# Rajesh_Jasti_17978253_Lab_1.net
KiCad netlist of a schematic drawn in Altium Designer
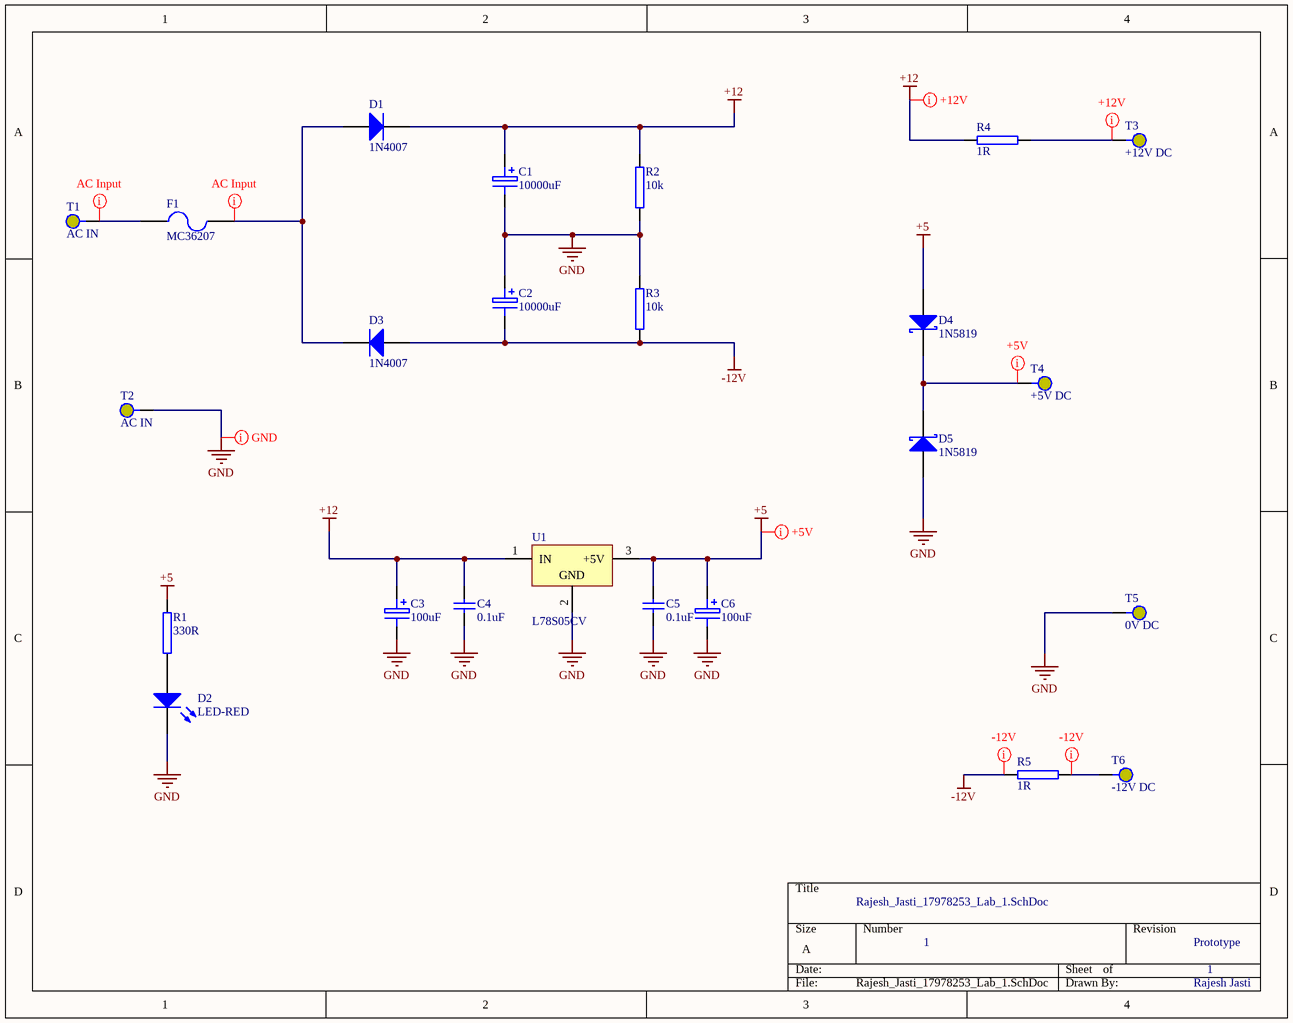
[diagram p0: Rajesh_Jasti_17978253_Lab_1.SchDoc]

(export (version "E")
  (design (tool "Eeschema 10.0.6"))
  (components
    (comp (ref "C1")
      (value "10000uF")
      (footprint "CAPP18-7.5mm")
      (description "Polarized Aluminum Capacitor, Through Hole, Pitch 7.5mml, Body 18mm(Dia)")
      (libsource (lib "Resistors and Capacitors") (part "CAPACITOR 10000uF"))
    )
    (comp (ref "C2")
      (value "10000uF")
      (footprint "CAPP18-7.5mm")
      (description "Polarized Aluminum Capacitor, Through Hole, Pitch 7.5mml, Body 18mm(Dia)")
      (libsource (lib "Resistors and Capacitors") (part "CAPACITOR 10000uF"))
    )
    (comp (ref "C3")
      (value "100uF")
      (footprint "CAPP150-300_AUT")
      (description "Polarized Aluminum Capacitor, Through Hole, Pitch 150mil, Body 300mil (Dia)")
      (libsource (lib "Resistors and Capacitors") (part "CAPP150-300"))
    )
    (comp (ref "C4")
      (value "0.1uF")
      (footprint "RAD-0.1_AUT")
      (description "Non Polarized Capacitor, Multilayer Ceramic Dipped Radial, Pitch 100mil")
      (libsource (lib "Resistors and Capacitors") (part "CAPN RAD0.1"))
    )
    (comp (ref "C5")
      (value "0.1uF")
      (footprint "RAD-0.1_AUT")
      (description "Non Polarized Capacitor, Multilayer Ceramic Dipped Radial, Pitch 100mil")
      (libsource (lib "Resistors and Capacitors") (part "CAPN RAD0.1"))
    )
    (comp (ref "C6")
      (value "100uF")
      (footprint "CAPP150-300_AUT")
      (description "Polarized Aluminum Capacitor, Through Hole, Pitch 150mil, Body 300mil (Dia)")
      (libsource (lib "Resistors and Capacitors") (part "CAPP150-300"))
    )
    (comp (ref "D1")
      (value "1N4007")
      (footprint "DIODE0.4_AUT")
      (description "Diode, Standard, 1A, 1000v")
      (libsource (lib "Diodes") (part "1N4007"))
    )
    (comp (ref "D2")
      (value "LED-RED")
      (footprint "LED3MM_R_AUT")
      (description "3mm RED LED, Through Hole")
      (libsource (lib "LEDs") (part "3mm LED-RED"))
    )
    (comp (ref "D3")
      (value "1N4007")
      (footprint "DIODE0.4_AUT")
      (description "Diode, Standard, 1A, 1000v")
      (libsource (lib "Diodes") (part "1N4007"))
    )
    (comp (ref "D4")
      (value "1N5819")
      (footprint "DIODE0.4_AUT")
      (description "Schottky Diode, 1A,40v")
      (libsource (lib "Diodes") (part "1N5819"))
    )
    (comp (ref "D5")
      (value "1N5819")
      (footprint "DIODE0.4_AUT")
      (description "Schottky Diode, 1A,40v")
      (libsource (lib "Diodes") (part "1N5819"))
    )
    (comp (ref "F1")
      (value "MC36207")
      (footprint "MC36207")
      (description "Fuse, PTC Reset, 200mA Hold, 400mA Tripping, 30v")
      (libsource (lib "Fuses") (part "MC36207"))
    )
    (comp (ref "R1")
      (value "330R")
      (footprint "AXIAL-0.4AUT")
      (description "Resistor, Through Hole, Pitch 400mil")
      (libsource (lib "Resistors and Capacitors") (part "Resistor 1/4W"))
    )
    (comp (ref "R2")
      (value "10k")
      (footprint "AXIAL-0.4AUT")
      (description "Resistor, Through Hole, Pitch 400mil")
      (libsource (lib "Resistors and Capacitors") (part "Resistor 1/4W"))
    )
    (comp (ref "R3")
      (value "10k")
      (footprint "AXIAL-0.4AUT")
      (description "Resistor, Through Hole, Pitch 400mil")
      (libsource (lib "Resistors and Capacitors") (part "Resistor 1/4W"))
    )
    (comp (ref "R4")
      (value "1R")
      (footprint "AXIAL-0.5AUT")
      (description "Resistor, Through Hole, Pitch 500mil")
      (libsource (lib "Resistors and Capacitors") (part "Resistor 1/2W"))
    )
    (comp (ref "R5")
      (value "1R")
      (footprint "AXIAL-0.5AUT")
      (description "Resistor, Through Hole, Pitch 500mil")
      (libsource (lib "Resistors and Capacitors") (part "Resistor 1/2W"))
    )
    (comp (ref "T1")
      (value "AC IN")
      (footprint "PAD3_AUT")
      (description "Terminal, Pad 200x250mil, Hole 62mil")
      (libsource (lib "Connectors") (part "Terminal3"))
    )
    (comp (ref "T2")
      (value "AC IN")
      (footprint "PAD3_AUT")
      (description "Terminal, Pad 200x250mil, Hole 62mil")
      (libsource (lib "Connectors") (part "Terminal3"))
    )
    (comp (ref "T3")
      (value "+12V DC")
      (footprint "PAD3_AUT")
      (description "Terminal, Pad 200x250mil, Hole 62mil")
      (libsource (lib "Connectors") (part "Terminal3"))
    )
    (comp (ref "T4")
      (value "+5V DC")
      (footprint "PAD3_AUT")
      (description "Terminal, Pad 200x250mil, Hole 62mil")
      (libsource (lib "Connectors") (part "Terminal3"))
    )
    (comp (ref "T5")
      (value "0V DC")
      (footprint "PAD3_AUT")
      (description "Terminal, Pad 200x250mil, Hole 62mil")
      (libsource (lib "Connectors") (part "Terminal3"))
    )
    (comp (ref "T6")
      (value "-12V DC")
      (footprint "PAD3_AUT")
      (description "Terminal, Pad 200x250mil, Hole 62mil")
      (libsource (lib "Connectors") (part "Terminal3"))
    )
    (comp (ref "U1")
      (value "L78S05CV")
      (footprint "TO-220H")
      (description "5V, 2A, LDO, TO-220-3")
      (libsource (lib "Power Management") (part "L78S05CV"))
    )
  )
  (nets
    (net (code "1") (name "+5") (class "Default")
      (node (ref "C5") (pin "2") (pinfunction "2_2") (pintype "passive"))
      (node (ref "C6") (pin "1") (pinfunction "1_1") (pintype "passive"))
      (node (ref "D4") (pin "A") (pinfunction "A_A") (pintype "passive"))
      (node (ref "R1") (pin "2") (pinfunction "2_2") (pintype "passive"))
      (node (ref "U1") (pin "3") (pinfunction "+5V_3") (pintype "power_in"))
    )
    (net (code "2") (name "+12") (class "Default")
      (node (ref "C1") (pin "1") (pinfunction "1_1") (pintype "passive"))
      (node (ref "C3") (pin "1") (pinfunction "1_1") (pintype "passive"))
      (node (ref "C4") (pin "2") (pinfunction "2_2") (pintype "passive"))
      (node (ref "D1") (pin "K") (pinfunction "K_K") (pintype "passive"))
      (node (ref "R2") (pin "2") (pinfunction "2_2") (pintype "passive"))
      (node (ref "R4") (pin "1") (pinfunction "1_1") (pintype "passive"))
      (node (ref "U1") (pin "1") (pinfunction "IN_1") (pintype "power_in"))
    )
    (net (code "3") (name "-12V") (class "Default")
      (node (ref "C2") (pin "2") (pinfunction "2_2") (pintype "passive"))
      (node (ref "D3") (pin "A") (pinfunction "A_A") (pintype "passive"))
      (node (ref "R3") (pin "1") (pinfunction "1_1") (pintype "passive"))
      (node (ref "R5") (pin "1") (pinfunction "1_1") (pintype "passive"))
    )
    (net (code "4") (name "GND") (class "Default")
      (node (ref "C1") (pin "2") (pinfunction "2_2") (pintype "passive"))
      (node (ref "C2") (pin "1") (pinfunction "1_1") (pintype "passive"))
      (node (ref "C3") (pin "2") (pinfunction "2_2") (pintype "passive"))
      (node (ref "C4") (pin "1") (pinfunction "1_1") (pintype "passive"))
      (node (ref "C5") (pin "1") (pinfunction "1_1") (pintype "passive"))
      (node (ref "C6") (pin "2") (pinfunction "2_2") (pintype "passive"))
      (node (ref "D2") (pin "K") (pinfunction "K_K") (pintype "passive"))
      (node (ref "D5") (pin "A") (pinfunction "A_A") (pintype "passive"))
      (node (ref "R2") (pin "1") (pinfunction "1_1") (pintype "passive"))
      (node (ref "R3") (pin "2") (pinfunction "2_2") (pintype "passive"))
      (node (ref "T2") (pin "1") (pintype "passive"))
      (node (ref "T5") (pin "1") (pintype "passive"))
      (node (ref "U1") (pin "2") (pinfunction "GND_2") (pintype "power_in"))
    )
    (net (code "5") (name "Net-(D1-PadA)") (class "Default")
      (node (ref "D1") (pin "A") (pinfunction "A_A") (pintype "passive"))
      (node (ref "D3") (pin "K") (pinfunction "K_K") (pintype "passive"))
      (node (ref "F1") (pin "2") (pinfunction "2_2") (pintype "passive"))
    )
    (net (code "6") (name "Net-(D2-PadA)") (class "Default")
      (node (ref "D2") (pin "A") (pinfunction "A_A") (pintype "passive"))
      (node (ref "R1") (pin "1") (pinfunction "1_1") (pintype "passive"))
    )
    (net (code "7") (name "Net-(D4-PadK)") (class "Default")
      (node (ref "D4") (pin "K") (pinfunction "K_K") (pintype "passive"))
      (node (ref "D5") (pin "K") (pinfunction "K_K") (pintype "passive"))
      (node (ref "T4") (pin "1") (pintype "passive"))
    )
    (net (code "8") (name "Net-(F1-Pad1)") (class "Default")
      (node (ref "F1") (pin "1") (pinfunction "1_1") (pintype "passive"))
      (node (ref "T1") (pin "1") (pintype "passive"))
    )
    (net (code "9") (name "Net-(R4-Pad2)") (class "Default")
      (node (ref "R4") (pin "2") (pinfunction "2_2") (pintype "passive"))
      (node (ref "T3") (pin "1") (pintype "passive"))
    )
    (net (code "10") (name "Net-(R5-Pad2)") (class "Default")
      (node (ref "R5") (pin "2") (pinfunction "2_2") (pintype "passive"))
      (node (ref "T6") (pin "1") (pintype "passive"))
    )
  )
)
